# Industrial-Controller_PWR_Switch.net
KiCad netlist of a schematic drawn in Altium Designer
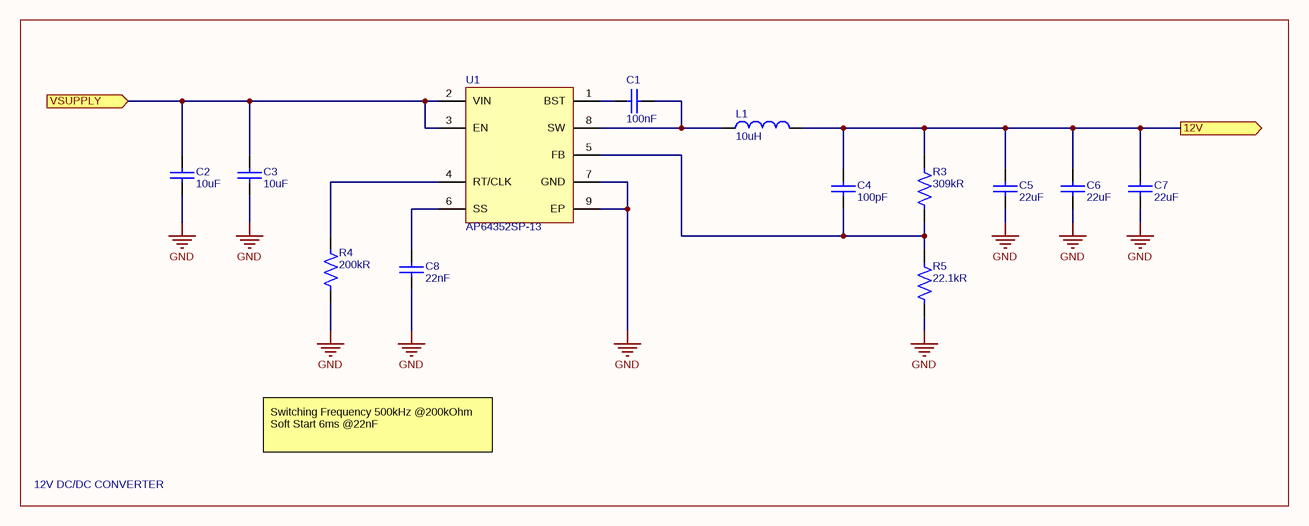
[diagram p0: Industrial-Controller_PWR_Switch.SchDoc]

(export (version "E")
  (design (tool "Eeschema 10.0.6"))
  (components
    (comp (ref "C1")
      (value "100nF")
      (footprint "CAP_0603")
      (description "CAP CER 0.1UF 50V X7R 0603")
      (fields (field (name "TOLERANCE") "10%"))
      (libsource (lib "Door_Controller_Single") (part "CL10B104KB8NNNL"))
    )
    (comp (ref "C2")
      (value "10uF")
      (footprint "CAP_1210")
      (description "CAP CER 10UF 50V X7R 1210")
      (fields (field (name "TOLERANCE") "10%"))
      (libsource (lib "Door_Controller_Single") (part "CL32B106KBJNNWE"))
    )
    (comp (ref "C3")
      (value "10uF")
      (footprint "CAP_1210")
      (description "CAP CER 10UF 50V X7R 1210")
      (fields (field (name "TOLERANCE") "10%"))
      (libsource (lib "Door_Controller_Single") (part "CL32B106KBJNNWE"))
    )
    (comp (ref "C4")
      (value "100pF")
      (footprint "CAP_0603")
      (description "CAP CER 100PF 50V X7R 0603")
      (fields (field (name "TOLERANCE") "10%"))
      (libsource (lib "Door_Controller_Single") (part "CL10B101KB8NFNC"))
    )
    (comp (ref "C5")
      (value "22uF")
      (footprint "CAP_1210")
      (description "CAP CER 22UF 25V X7R 1210")
      (fields (field (name "TOLERANCE") "10%"))
      (libsource (lib "Door_Controller_Single") (part "CL32B226KAJNNNE"))
    )
    (comp (ref "C6")
      (value "22uF")
      (footprint "CAP_1210")
      (description "CAP CER 22UF 25V X7R 1210")
      (fields (field (name "TOLERANCE") "10%"))
      (libsource (lib "Door_Controller_Single") (part "CL32B226KAJNNNE"))
    )
    (comp (ref "C7")
      (value "22uF")
      (footprint "CAP_1210")
      (description "CAP CER 22UF 25V X7R 1210")
      (fields (field (name "TOLERANCE") "10%"))
      (libsource (lib "Door_Controller_Single") (part "CL32B226KAJNNNE"))
    )
    (comp (ref "C8")
      (value "22nF")
      (footprint "CAP_0603")
      (description "CAP CER 0.022UF 50V X7R 0603")
      (fields (field (name "TOLERANCE") "10%"))
      (libsource (lib "Door_Controller_Single") (part "CL10B223KB8WPNC"))
    )
    (comp (ref "L1")
      (value "10uH")
      (footprint "SRU1048")
      (description "FIXED IND 10UH 4.5A 18.5MOHM SMD")
      (fields (field (name "TOLERANCE") "30%"))
      (libsource (lib "Door_Controller_Single") (part "SRU1048-100Y"))
    )
    (comp (ref "R3")
      (value "309kR")
      (footprint "RES_0603")
      (description "RES 309K OHM 1% 1/10W 0603")
      (fields (field (name "TOLERANCE") "1%"))
      (libsource (lib "Door_Controller_Single") (part "RC0603FR-07309KL"))
    )
    (comp (ref "R4")
      (value "200kR")
      (footprint "RES_0603")
      (description "RES 200K OHM 1% 1/10W 0603")
      (fields (field (name "TOLERANCE") "1%"))
      (libsource (lib "Door_Controller_Single") (part "RC0603FR-07200KL"))
    )
    (comp (ref "R5")
      (value "22.1kR")
      (footprint "RES_0603")
      (description "RES 22.1K OHM 1% 1/10W 0603")
      (fields (field (name "TOLERANCE") "1%"))
      (libsource (lib "Door_Controller_Single") (part "RC0603FR-0722K1L"))
    )
    (comp (ref "U1")
      (value "AP64352SP-13")
      (footprint "SOIC-8EP_150mil")
      (description "IC DCDC CONV BUCK 3.5A SO-8EP")
      (libsource (lib "Door_Controller_Single") (part "AP64352SP-13"))
    )
  )
  (nets
    (net (code "1") (name "/12V") (class "Default")
      (node (ref "C4") (pin "2") (pinfunction "2_2") (pintype "passive"))
      (node (ref "C5") (pin "2") (pinfunction "2_2") (pintype "passive"))
      (node (ref "C6") (pin "2") (pinfunction "2_2") (pintype "passive"))
      (node (ref "C7") (pin "2") (pinfunction "2_2") (pintype "passive"))
      (node (ref "L1") (pin "2") (pinfunction "2_2") (pintype "passive"))
      (node (ref "R3") (pin "1") (pinfunction "1_1") (pintype "passive"))
    )
    (net (code "2") (name "/VSUPPLY") (class "Default")
      (node (ref "C2") (pin "2") (pinfunction "2_2") (pintype "passive"))
      (node (ref "C3") (pin "2") (pinfunction "2_2") (pintype "passive"))
      (node (ref "U1") (pin "2") (pinfunction "VIN_2") (pintype "passive"))
      (node (ref "U1") (pin "3") (pinfunction "EN_3") (pintype "passive"))
    )
    (net (code "3") (name "GND") (class "Default")
      (node (ref "C2") (pin "1") (pinfunction "1_1") (pintype "passive"))
      (node (ref "C3") (pin "1") (pinfunction "1_1") (pintype "passive"))
      (node (ref "C5") (pin "1") (pinfunction "1_1") (pintype "passive"))
      (node (ref "C6") (pin "1") (pinfunction "1_1") (pintype "passive"))
      (node (ref "C7") (pin "1") (pinfunction "1_1") (pintype "passive"))
      (node (ref "C8") (pin "1") (pinfunction "1_1") (pintype "passive"))
      (node (ref "R4") (pin "2") (pinfunction "2_2") (pintype "passive"))
      (node (ref "R5") (pin "2") (pinfunction "2_2") (pintype "passive"))
      (node (ref "U1") (pin "7") (pinfunction "GND_7") (pintype "passive"))
      (node (ref "U1") (pin "9") (pinfunction "EP_9") (pintype "passive"))
    )
    (net (code "4") (name "Net-(U1-BST)") (class "Default")
      (node (ref "C1") (pin "2") (pinfunction "2_2") (pintype "passive"))
      (node (ref "U1") (pin "1") (pinfunction "BST_1") (pintype "passive"))
    )
    (net (code "5") (name "Net-(U1-FB)") (class "Default")
      (node (ref "C4") (pin "1") (pinfunction "1_1") (pintype "passive"))
      (node (ref "R3") (pin "2") (pinfunction "2_2") (pintype "passive"))
      (node (ref "R5") (pin "1") (pinfunction "1_1") (pintype "passive"))
      (node (ref "U1") (pin "5") (pinfunction "FB_5") (pintype "passive"))
    )
    (net (code "6") (name "Net-(U1-RT{slash}CLK)") (class "Default")
      (node (ref "R4") (pin "1") (pinfunction "1_1") (pintype "passive"))
      (node (ref "U1") (pin "4") (pinfunction "RT/CLK_4") (pintype "passive"))
    )
    (net (code "7") (name "Net-(U1-SS)") (class "Default")
      (node (ref "C8") (pin "2") (pinfunction "2_2") (pintype "passive"))
      (node (ref "U1") (pin "6") (pinfunction "SS_6") (pintype "passive"))
    )
    (net (code "8") (name "Net-(U1-SW)") (class "Default")
      (node (ref "C1") (pin "1") (pinfunction "1_1") (pintype "passive"))
      (node (ref "L1") (pin "1") (pinfunction "1_1") (pintype "passive"))
      (node (ref "U1") (pin "8") (pinfunction "SW_8") (pintype "passive"))
    )
  )
)
